# classdamp.net
KiCad netlist of a schematic drawn in EAGLE
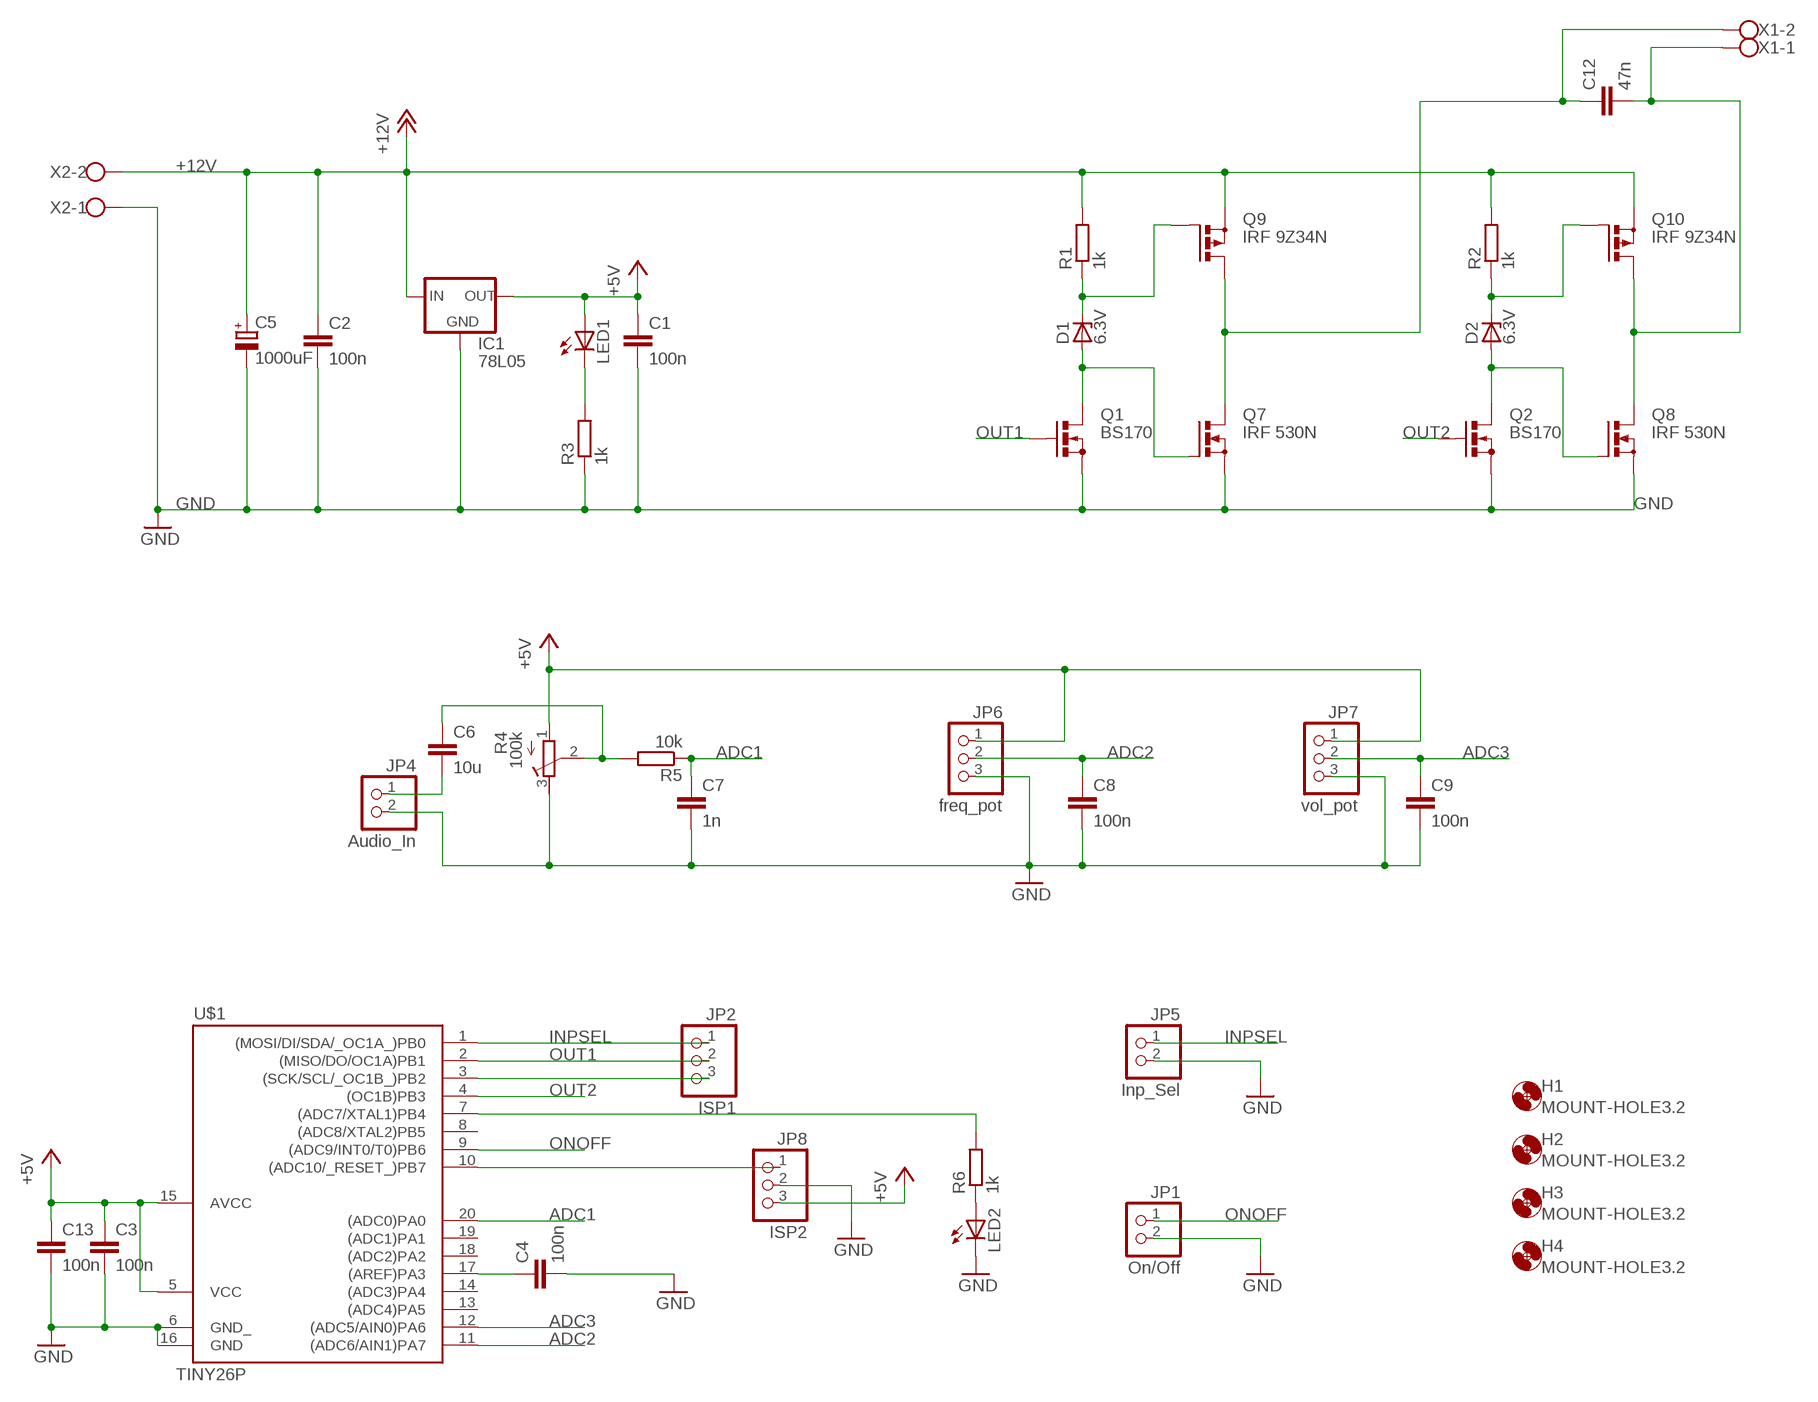
[diagram p0: schematic, sheet 1]

(export (version "E")
  (design (tool "Eeschema 10.0.6"))
  (components
    (comp (ref "C1")
      (value "100n")
      (footprint "eagle-import:C0805K")
      (libsource (lib "eagle-import") (part "C-EUC0805K"))
    )
    (comp (ref "C2")
      (value "100n")
      (footprint "eagle-import:C0805K")
      (libsource (lib "eagle-import") (part "C-EUC0805K"))
    )
    (comp (ref "C3")
      (value "100n")
      (footprint "eagle-import:C0805K")
      (libsource (lib "eagle-import") (part "C-EUC0805K"))
    )
    (comp (ref "C4")
      (value "100n")
      (footprint "eagle-import:C0805K")
      (libsource (lib "eagle-import") (part "C-EUC0805K"))
    )
    (comp (ref "C5")
      (value "1000uF")
      (footprint "eagle-import:E5-8,5")
      (libsource (lib "eagle-import") (part "CPOL-EUE5-8.5"))
    )
    (comp (ref "C6")
      (value "10u")
      (footprint "eagle-import:C0805K")
      (libsource (lib "eagle-import") (part "C-EUC0805K"))
    )
    (comp (ref "C7")
      (value "1n")
      (footprint "eagle-import:C0805K")
      (libsource (lib "eagle-import") (part "C-EUC0805K"))
    )
    (comp (ref "C8")
      (value "100n")
      (footprint "eagle-import:C0805K")
      (libsource (lib "eagle-import") (part "C-EUC0805K"))
    )
    (comp (ref "C9")
      (value "100n")
      (footprint "eagle-import:C0805K")
      (libsource (lib "eagle-import") (part "C-EUC0805K"))
    )
    (comp (ref "C12")
      (value "47n")
      (footprint "eagle-import:C5B3.5")
      (libsource (lib "eagle-import") (part "C5/3.5"))
    )
    (comp (ref "C13")
      (value "100n")
      (footprint "eagle-import:C0805K")
      (libsource (lib "eagle-import") (part "C-EUC0805K"))
    )
    (comp (ref "D1")
      (value "6.3V")
      (footprint "eagle-import:ZDIO-5")
      (libsource (lib "eagle-import") (part "ZENER-DIODEZD-5"))
    )
    (comp (ref "D2")
      (value "6.3V")
      (footprint "eagle-import:ZDIO-5")
      (libsource (lib "eagle-import") (part "ZENER-DIODEZD-5"))
    )
    (comp (ref "H1")
      (value "MOUNT-HOLE3.2")
      (footprint "eagle-import:3,2")
      (libsource (lib "eagle-import") (part "MOUNT-HOLE3.2"))
    )
    (comp (ref "H2")
      (value "MOUNT-HOLE3.2")
      (footprint "eagle-import:3,2")
      (libsource (lib "eagle-import") (part "MOUNT-HOLE3.2"))
    )
    (comp (ref "H3")
      (value "MOUNT-HOLE3.2")
      (footprint "eagle-import:3,2")
      (libsource (lib "eagle-import") (part "MOUNT-HOLE3.2"))
    )
    (comp (ref "H4")
      (value "MOUNT-HOLE3.2")
      (footprint "eagle-import:3,2")
      (libsource (lib "eagle-import") (part "MOUNT-HOLE3.2"))
    )
    (comp (ref "IC1")
      (value "78L05")
      (footprint "eagle-import:78LXX")
      (libsource (lib "eagle-import") (part "78LXX"))
    )
    (comp (ref "JP1")
      (value "On/Off")
      (footprint "eagle-import:1X02")
      (libsource (lib "eagle-import") (part "PINHD-1X2"))
    )
    (comp (ref "JP2")
      (value "ISP1")
      (footprint "eagle-import:1X03")
      (libsource (lib "eagle-import") (part "PINHD-1X3"))
    )
    (comp (ref "JP4")
      (value "Audio_In")
      (footprint "eagle-import:1X02")
      (libsource (lib "eagle-import") (part "PINHD-1X2"))
    )
    (comp (ref "JP5")
      (value "Inp_Sel")
      (footprint "eagle-import:1X02")
      (libsource (lib "eagle-import") (part "PINHD-1X2"))
    )
    (comp (ref "JP6")
      (value "freq_pot")
      (footprint "eagle-import:1X03")
      (libsource (lib "eagle-import") (part "PINHD-1X3"))
    )
    (comp (ref "JP7")
      (value "vol_pot")
      (footprint "eagle-import:1X03")
      (libsource (lib "eagle-import") (part "PINHD-1X3"))
    )
    (comp (ref "JP8")
      (value "ISP2")
      (footprint "eagle-import:1X03")
      (libsource (lib "eagle-import") (part "PINHD-1X3"))
    )
    (comp (ref "LED1")
      (value "LEDSML0805")
      (footprint "eagle-import:SML0805")
      (libsource (lib "eagle-import") (part "LEDSML0805"))
    )
    (comp (ref "LED2")
      (value "LEDSML0805")
      (footprint "eagle-import:SML0805")
      (libsource (lib "eagle-import") (part "LEDSML0805"))
    )
    (comp (ref "Q1")
      (value "BS170")
      (footprint "eagle-import:SOT54E")
      (libsource (lib "eagle-import") (part "BS170"))
    )
    (comp (ref "Q2")
      (value "BS170")
      (footprint "eagle-import:SOT54E")
      (libsource (lib "eagle-import") (part "BS170"))
    )
    (comp (ref "Q7")
      (value "IRF 530N")
      (footprint "eagle-import:TO220BV")
      (libsource (lib "eagle-import") (part "PMOSFET_NTO220BV"))
    )
    (comp (ref "Q8")
      (value "IRF 530N")
      (footprint "eagle-import:TO220BV")
      (libsource (lib "eagle-import") (part "PMOSFET_NTO220BV"))
    )
    (comp (ref "Q9")
      (value "IRF 9Z34N")
      (footprint "eagle-import:TO220BV")
      (libsource (lib "eagle-import") (part "PMOSFET_PTO220BV"))
    )
    (comp (ref "Q10")
      (value "IRF 9Z34N")
      (footprint "eagle-import:TO220BV")
      (libsource (lib "eagle-import") (part "PMOSFET_PTO220BV"))
    )
    (comp (ref "R1")
      (value "1k")
      (footprint "eagle-import:R0805")
      (libsource (lib "eagle-import") (part "R-EU_R0805"))
    )
    (comp (ref "R2")
      (value "1k")
      (footprint "eagle-import:R0805")
      (libsource (lib "eagle-import") (part "R-EU_R0805"))
    )
    (comp (ref "R3")
      (value "1k")
      (footprint "eagle-import:R0805")
      (libsource (lib "eagle-import") (part "R-EU_R0805"))
    )
    (comp (ref "R4")
      (value "100k")
      (footprint "eagle-import:RTRIM64W")
      (libsource (lib "eagle-import") (part "R-TRIMM64W"))
    )
    (comp (ref "R5")
      (value "10k")
      (footprint "eagle-import:R0805")
      (libsource (lib "eagle-import") (part "R-EU_R0805"))
    )
    (comp (ref "R6")
      (value "1k")
      (footprint "eagle-import:R0805")
      (libsource (lib "eagle-import") (part "R-EU_R0805"))
    )
    (comp (ref "U$1")
      (value "TINY26P")
      (footprint "eagle-import:DIL20")
      (libsource (lib "eagle-import") (part "TINY26P"))
    )
    (comp (ref "X1")
      (value "W237-102")
      (footprint "eagle-import:W237-102")
      (fields (field (name "MPN") "237-102"))
      (libsource (lib "eagle-import") (part "W237-102"))
    )
    (comp (ref "X2")
      (value "W237-102")
      (footprint "eagle-import:W237-102")
      (fields (field (name "MPN") "237-102"))
      (libsource (lib "eagle-import") (part "W237-102"))
    )
  )
  (nets
    (net (code "1") (name "+5V") (class "Default")
      (node (ref "C1") (pin "1") (pinfunction "1_1") (pintype "passive"))
      (node (ref "C13") (pin "1") (pinfunction "1_1") (pintype "passive"))
      (node (ref "C3") (pin "1") (pinfunction "1_1") (pintype "passive"))
      (node (ref "IC1") (pin "OUT") (pinfunction "OUT_OUT") (pintype "passive"))
      (node (ref "JP6") (pin "1") (pinfunction "1_1") (pintype "passive"))
      (node (ref "JP7") (pin "1") (pinfunction "1_1") (pintype "passive"))
      (node (ref "JP8") (pin "3") (pinfunction "3_3") (pintype "passive"))
      (node (ref "LED1") (pin "A") (pinfunction "A_A") (pintype "passive"))
      (node (ref "R4") (pin "1") (pinfunction "E_1") (pintype "passive"))
      (node (ref "U$1") (pin "15") (pinfunction "AVCC_15") (pintype "power_in"))
      (node (ref "U$1") (pin "5") (pinfunction "VCC_5") (pintype "power_in"))
    )
    (net (code "2") (name "+12V") (class "Default")
      (node (ref "C2") (pin "1") (pinfunction "1_1") (pintype "passive"))
      (node (ref "C5") (pin "+") (pinfunction "+_+") (pintype "passive"))
      (node (ref "IC1") (pin "IN") (pinfunction "IN_IN") (pintype "input"))
      (node (ref "Q10") (pin "S") (pinfunction "S_S") (pintype "passive"))
      (node (ref "Q9") (pin "S") (pinfunction "S_S") (pintype "passive"))
      (node (ref "R1") (pin "2") (pinfunction "2_2") (pintype "passive"))
      (node (ref "R2") (pin "2") (pinfunction "2_2") (pintype "passive"))
      (node (ref "X2") (pin "2") (pinfunction "KL_2") (pintype "passive"))
    )
    (net (code "3") (name "/ADC1") (class "Default")
      (node (ref "C7") (pin "1") (pinfunction "1_1") (pintype "passive"))
      (node (ref "R5") (pin "1") (pinfunction "1_1") (pintype "passive"))
      (node (ref "U$1") (pin "20") (pinfunction "(ADC0)PA0_20") (pintype "bidirectional"))
    )
    (net (code "4") (name "/ADC2") (class "Default")
      (node (ref "C8") (pin "1") (pinfunction "1_1") (pintype "passive"))
      (node (ref "JP6") (pin "2") (pinfunction "2_2") (pintype "passive"))
      (node (ref "U$1") (pin "11") (pinfunction "(ADC6/AIN1)PA7_11") (pintype "bidirectional"))
    )
    (net (code "5") (name "/ADC3") (class "Default")
      (node (ref "C9") (pin "1") (pinfunction "1_1") (pintype "passive"))
      (node (ref "JP7") (pin "2") (pinfunction "2_2") (pintype "passive"))
      (node (ref "U$1") (pin "12") (pinfunction "(ADC5/AIN0)PA6_12") (pintype "bidirectional"))
    )
    (net (code "6") (name "/INPSEL") (class "Default")
      (node (ref "JP2") (pin "1") (pinfunction "1_1") (pintype "passive"))
      (node (ref "JP5") (pin "1") (pinfunction "1_1") (pintype "passive"))
      (node (ref "U$1") (pin "1") (pinfunction "(MOSI/DI/SDA/_OC1A_)PB0_1") (pintype "bidirectional"))
    )
    (net (code "7") (name "/ONOFF") (class "Default")
      (node (ref "JP1") (pin "1") (pinfunction "1_1") (pintype "passive"))
      (node (ref "U$1") (pin "9") (pinfunction "(ADC9/INT0/T0)PB6_9") (pintype "bidirectional"))
    )
    (net (code "8") (name "/OUT1") (class "Default")
      (node (ref "JP2") (pin "2") (pinfunction "2_2") (pintype "passive"))
      (node (ref "Q1") (pin "G") (pinfunction "G_G") (pintype "passive"))
      (node (ref "U$1") (pin "2") (pinfunction "(MISO/DO/OC1A)PB1_2") (pintype "bidirectional"))
    )
    (net (code "9") (name "/OUT2") (class "Default")
      (node (ref "Q2") (pin "G") (pinfunction "G_G") (pintype "passive"))
      (node (ref "U$1") (pin "4") (pinfunction "(OC1B)PB3_4") (pintype "bidirectional"))
    )
    (net (code "10") (name "GND") (class "Default")
      (node (ref "C1") (pin "2") (pinfunction "2_2") (pintype "passive"))
      (node (ref "C13") (pin "2") (pinfunction "2_2") (pintype "passive"))
      (node (ref "C2") (pin "2") (pinfunction "2_2") (pintype "passive"))
      (node (ref "C3") (pin "2") (pinfunction "2_2") (pintype "passive"))
      (node (ref "C4") (pin "2") (pinfunction "2_2") (pintype "passive"))
      (node (ref "C5") (pin "-") (pinfunction "-_-") (pintype "passive"))
      (node (ref "C7") (pin "2") (pinfunction "2_2") (pintype "passive"))
      (node (ref "C8") (pin "2") (pinfunction "2_2") (pintype "passive"))
      (node (ref "C9") (pin "2") (pinfunction "2_2") (pintype "passive"))
      (node (ref "IC1") (pin "GND") (pinfunction "GND_GND") (pintype "input"))
      (node (ref "JP1") (pin "2") (pinfunction "2_2") (pintype "passive"))
      (node (ref "JP4") (pin "2") (pinfunction "2_2") (pintype "passive"))
      (node (ref "JP5") (pin "2") (pinfunction "2_2") (pintype "passive"))
      (node (ref "JP6") (pin "3") (pinfunction "3_3") (pintype "passive"))
      (node (ref "JP7") (pin "3") (pinfunction "3_3") (pintype "passive"))
      (node (ref "JP8") (pin "2") (pinfunction "2_2") (pintype "passive"))
      (node (ref "LED2") (pin "C") (pinfunction "C_C") (pintype "passive"))
      (node (ref "Q1") (pin "S") (pinfunction "S_S") (pintype "passive"))
      (node (ref "Q2") (pin "S") (pinfunction "S_S") (pintype "passive"))
      (node (ref "Q7") (pin "S") (pinfunction "S_S") (pintype "passive"))
      (node (ref "Q8") (pin "S") (pinfunction "S_S") (pintype "passive"))
      (node (ref "R3") (pin "1") (pinfunction "1_1") (pintype "passive"))
      (node (ref "R4") (pin "3") (pinfunction "A_3") (pintype "passive"))
      (node (ref "U$1") (pin "16") (pinfunction "GND_16") (pintype "power_in"))
      (node (ref "U$1") (pin "6") (pinfunction "GND__6") (pintype "power_in"))
      (node (ref "X2") (pin "1") (pinfunction "KL_1") (pintype "passive"))
    )
    (net (code "11") (name "Net-(C6-Pad2)") (class "Default")
      (node (ref "C6") (pin "2") (pinfunction "2_2") (pintype "passive"))
      (node (ref "JP4") (pin "1") (pinfunction "1_1") (pintype "passive"))
    )
    (net (code "12") (name "Net-(D1-PadA)") (class "Default")
      (node (ref "D1") (pin "A") (pinfunction "A_A") (pintype "passive"))
      (node (ref "Q1") (pin "D") (pinfunction "D_D") (pintype "passive"))
      (node (ref "Q7") (pin "G") (pinfunction "G_G") (pintype "passive"))
    )
    (net (code "13") (name "Net-(D1-PadC)") (class "Default")
      (node (ref "D1") (pin "C") (pinfunction "C_C") (pintype "passive"))
      (node (ref "Q9") (pin "G") (pinfunction "G_G") (pintype "passive"))
      (node (ref "R1") (pin "1") (pinfunction "1_1") (pintype "passive"))
    )
    (net (code "14") (name "Net-(D2-PadA)") (class "Default")
      (node (ref "D2") (pin "A") (pinfunction "A_A") (pintype "passive"))
      (node (ref "Q2") (pin "D") (pinfunction "D_D") (pintype "passive"))
      (node (ref "Q8") (pin "G") (pinfunction "G_G") (pintype "passive"))
    )
    (net (code "15") (name "Net-(D2-PadC)") (class "Default")
      (node (ref "D2") (pin "C") (pinfunction "C_C") (pintype "passive"))
      (node (ref "Q10") (pin "G") (pinfunction "G_G") (pintype "passive"))
      (node (ref "R2") (pin "1") (pinfunction "1_1") (pintype "passive"))
    )
    (net (code "16") (name "Net-(LED1-PadC)") (class "Default")
      (node (ref "LED1") (pin "C") (pinfunction "C_C") (pintype "passive"))
      (node (ref "R3") (pin "2") (pinfunction "2_2") (pintype "passive"))
    )
    (net (code "17") (name "Net-(LED2-PadA)") (class "Default")
      (node (ref "LED2") (pin "A") (pinfunction "A_A") (pintype "passive"))
      (node (ref "R6") (pin "1") (pinfunction "1_1") (pintype "passive"))
    )
    (net (code "18") (name "Net-(R4-S)") (class "Default")
      (node (ref "C6") (pin "1") (pinfunction "1_1") (pintype "passive"))
      (node (ref "R4") (pin "2") (pinfunction "S_2") (pintype "passive"))
      (node (ref "R5") (pin "2") (pinfunction "2_2") (pintype "passive"))
    )
    (net (code "19") (name "Net-(U$1-(ADC7{slash}XTAL1)PB4)") (class "Default")
      (node (ref "R6") (pin "2") (pinfunction "2_2") (pintype "passive"))
      (node (ref "U$1") (pin "7") (pinfunction "(ADC7/XTAL1)PB4_7") (pintype "bidirectional"))
    )
    (net (code "20") (name "Net-(U$1-(ADC10{slash}_RESET_)PB7)") (class "Default")
      (node (ref "JP8") (pin "1") (pinfunction "1_1") (pintype "passive"))
      (node (ref "U$1") (pin "10") (pinfunction "(ADC10/_RESET_)PB7_10") (pintype "bidirectional"))
    )
    (net (code "21") (name "Net-(U$1-(AREF)PA3)") (class "Default")
      (node (ref "C4") (pin "1") (pinfunction "1_1") (pintype "passive"))
      (node (ref "U$1") (pin "17") (pinfunction "(AREF)PA3_17") (pintype "bidirectional"))
    )
    (net (code "22") (name "Net-(U$1-(SCK{slash}SCL{slash}_OC1B_)PB2)") (class "Default")
      (node (ref "JP2") (pin "3") (pinfunction "3_3") (pintype "passive"))
      (node (ref "U$1") (pin "3") (pinfunction "(SCK/SCL/_OC1B_)PB2_3") (pintype "bidirectional"))
    )
    (net (code "23") (name "Net-(X1A-KL)") (class "Default")
      (node (ref "C12") (pin "2") (pinfunction "2_2") (pintype "passive"))
      (node (ref "Q10") (pin "D") (pinfunction "D_D") (pintype "passive"))
      (node (ref "Q8") (pin "D") (pinfunction "D_D") (pintype "passive"))
      (node (ref "X1") (pin "1") (pinfunction "KL_1") (pintype "passive"))
    )
    (net (code "24") (name "Net-(X1B-KL)") (class "Default")
      (node (ref "C12") (pin "1") (pinfunction "1_1") (pintype "passive"))
      (node (ref "Q7") (pin "D") (pinfunction "D_D") (pintype "passive"))
      (node (ref "Q9") (pin "D") (pinfunction "D_D") (pintype "passive"))
      (node (ref "X1") (pin "2") (pinfunction "KL_2") (pintype "passive"))
    )
    (net (code "25") (name "unconnected-(U$1-(ADC1)PA1-Pad19)") (class "Default")
      (node (ref "U$1") (pin "19") (pinfunction "(ADC1)PA1_19") (pintype "bidirectional"))
    )
    (net (code "26") (name "unconnected-(U$1-(ADC2)PA2-Pad18)") (class "Default")
      (node (ref "U$1") (pin "18") (pinfunction "(ADC2)PA2_18") (pintype "bidirectional"))
    )
    (net (code "27") (name "unconnected-(U$1-(ADC3)PA4-Pad14)") (class "Default")
      (node (ref "U$1") (pin "14") (pinfunction "(ADC3)PA4_14") (pintype "bidirectional"))
    )
    (net (code "28") (name "unconnected-(U$1-(ADC4)PA5-Pad13)") (class "Default")
      (node (ref "U$1") (pin "13") (pinfunction "(ADC4)PA5_13") (pintype "bidirectional"))
    )
    (net (code "29") (name "unconnected-(U$1-(ADC8{slash}XTAL2)PB5-Pad8)") (class "Default")
      (node (ref "U$1") (pin "8") (pinfunction "(ADC8/XTAL2)PB5_8") (pintype "bidirectional"))
    )
  )
)
